# power_supply.net
KiCad netlist of a schematic drawn in Altium Designer
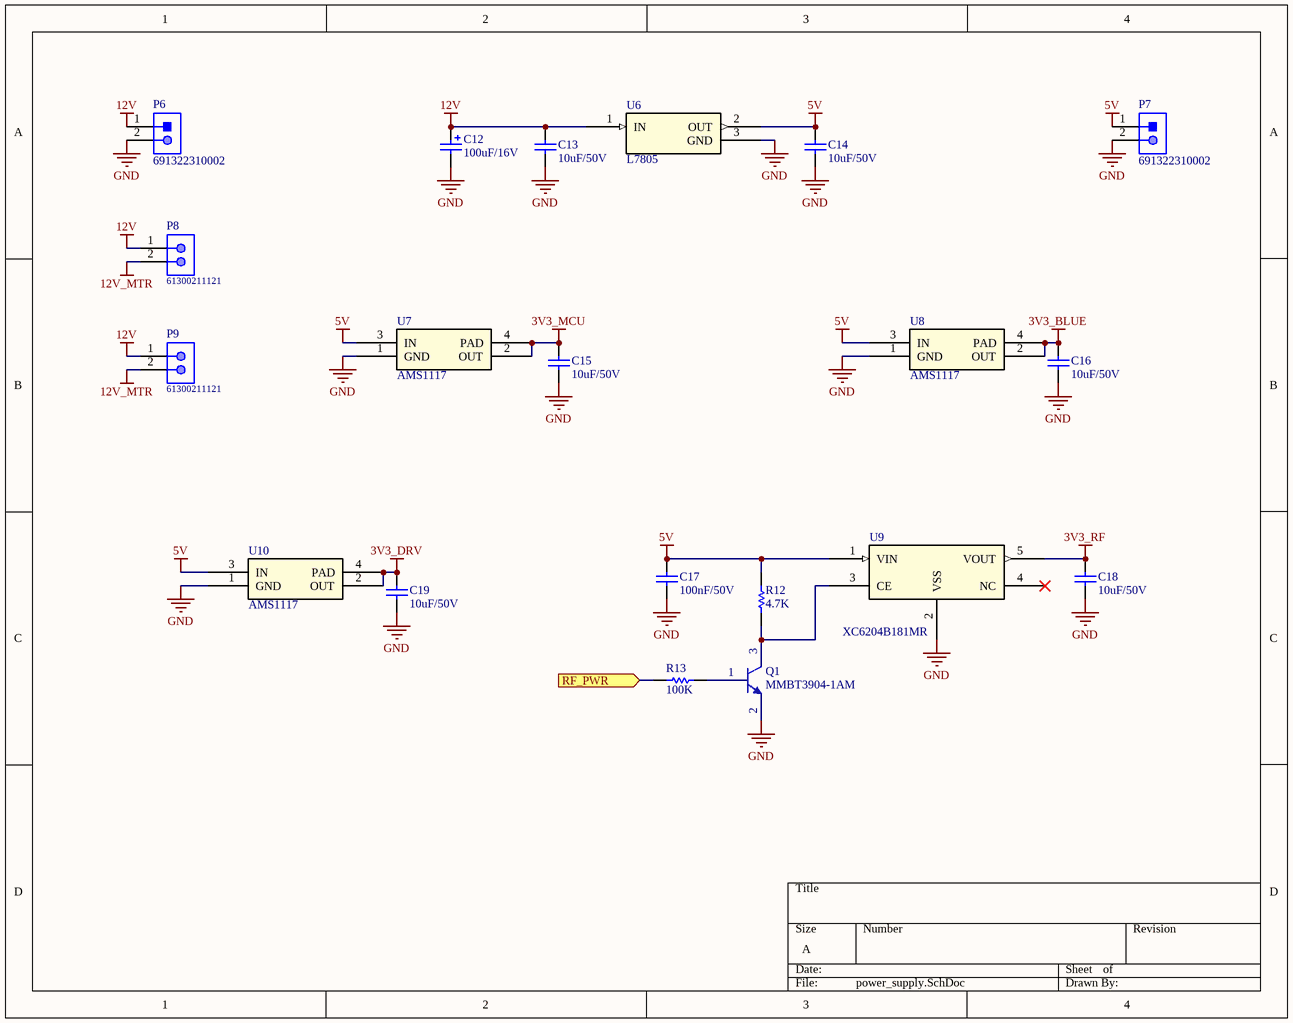
[diagram p0: power_supply.SchDoc]

(export (version "E")
  (design (tool "Eeschema 10.0.6"))
  (components
    (comp (ref "C12")
      (value "100uF/16V")
      (footprint "CAP-SM-AL-SIZE-D-D6L6")
      (description "CAP ALUM 100UF 20% 16V SMD")
      (fields
        (field (name "MANUFACTURER") "Nichicon")
        (field (name "MANUFACTURER PART NUMBER") "UWX1C101MCL1GB")
      )
      (libsource (lib "Capacitor") (part "Cap-Al-100uF-16V-D6L5"))
    )
    (comp (ref "C13")
      (value "10uF/50V")
      (footprint "CAP-SM-0805")
      (description "CAP CER 10UF 50V X5R 0805")
      (fields
        (field (name "MANUFACTURER") "Yageo")
        (field (name "MANUFACTURER PART NUMBER") "CC0805KKX5R9BB106")
      )
      (libsource (lib "Capacitor") (part "Cap-10uF-50V-0805"))
    )
    (comp (ref "C14")
      (value "10uF/50V")
      (footprint "CAP-SM-0805")
      (description "CAP CER 10UF 50V X5R 0805")
      (fields
        (field (name "MANUFACTURER") "Yageo")
        (field (name "MANUFACTURER PART NUMBER") "CC0805KKX5R9BB106")
      )
      (libsource (lib "Capacitor") (part "Cap-10uF-50V-0805"))
    )
    (comp (ref "C15")
      (value "10uF/50V")
      (footprint "CAP-SM-0805")
      (description "CAP CER 10UF 50V X5R 0805")
      (fields
        (field (name "MANUFACTURER") "Yageo")
        (field (name "MANUFACTURER PART NUMBER") "CC0805KKX5R9BB106")
      )
      (libsource (lib "Capacitor") (part "Cap-10uF-50V-0805"))
    )
    (comp (ref "C16")
      (value "10uF/50V")
      (footprint "CAP-SM-0805")
      (description "CAP CER 10UF 50V X5R 0805")
      (fields
        (field (name "MANUFACTURER") "Yageo")
        (field (name "MANUFACTURER PART NUMBER") "CC0805KKX5R9BB106")
      )
      (libsource (lib "Capacitor") (part "Cap-10uF-50V-0805"))
    )
    (comp (ref "C17")
      (value "100nF/50V")
      (footprint "CAP-SM-0805")
      (description "CAP CER 0.1UF 50V Y5V 0805")
      (fields
        (field (name "MANUFACTURER") "Samsung Electro-Mechanics")
        (field (name "MANUFACTURER PART NUMBER") "CL21F104ZBCNNNC")
      )
      (libsource (lib "Capacitor") (part "Cap-100nF-50V-0805"))
    )
    (comp (ref "C18")
      (value "10uF/50V")
      (footprint "CAP-SM-0805")
      (description "CAP CER 10UF 50V X5R 0805")
      (fields
        (field (name "MANUFACTURER") "Yageo")
        (field (name "MANUFACTURER PART NUMBER") "CC0805KKX5R9BB106")
      )
      (libsource (lib "Capacitor") (part "Cap-10uF-50V-0805"))
    )
    (comp (ref "C19")
      (value "10uF/50V")
      (footprint "CAP-SM-0805")
      (description "CAP CER 10UF 50V X5R 0805")
      (fields
        (field (name "MANUFACTURER") "Yageo")
        (field (name "MANUFACTURER PART NUMBER") "CC0805KKX5R9BB106")
      )
      (libsource (lib "Capacitor") (part "Cap-10uF-50V-0805"))
    )
    (comp (ref "P6")
      (value "691322310002")
      (footprint "691322310002")
      (description "WR-TBL Serie 322 Horizontal PCB Header, Pluggable, pitch 3.81mm, 2p")
      (fields (field (name "PUBLISHER") "Wurth Elektronik"))
      (libsource (lib "Wire_Protector") (part "691322310002"))
    )
    (comp (ref "P7")
      (value "691322310002")
      (footprint "691322310002")
      (description "WR-TBL Serie 322 Horizontal PCB Header, Pluggable, pitch 3.81mm, 2p")
      (fields (field (name "PUBLISHER") "Wurth Elektronik"))
      (libsource (lib "Wire_Protector") (part "691322310002"))
    )
    (comp (ref "P8")
      (value "61300211121")
      (footprint "61300211121")
      (description "WR-PHD Pin Header, THT, pitch 2.54mm, Single Row, Vertical, 2p")
      (fields (field (name "MANUFACTURER") "Wurth Elektronik"))
      (libsource (lib "Pluggable_Connector") (part "61300211121"))
    )
    (comp (ref "P9")
      (value "61300211121")
      (footprint "61300211121")
      (description "WR-PHD Pin Header, THT, pitch 2.54mm, Single Row, Vertical, 2p")
      (fields (field (name "MANUFACTURER") "Wurth Elektronik"))
      (libsource (lib "Pluggable_Connector") (part "61300211121"))
    )
    (comp (ref "Q1")
      (value "MMBT3904-1AM")
      (footprint "SOT23_NEX")
      (libsource (lib "Semiconductor") (part "MMBT3904-1AM"))
    )
    (comp (ref "R12")
      (value "4.7K")
      (footprint "Resistor:RES-SM-0805")
      (description "RES SMD 4.7K OHM 5% 1/8W 0805")
      (fields
        (field (name "MANUFACTURER") "Yageo")
        (field (name "MANUFACTURER PART NUMBER") "RC0805JR-074K7L")
      )
      (libsource (lib "Resistor") (part "Res-4.7K-0805"))
    )
    (comp (ref "R13")
      (value "100K")
      (footprint "Resistor:RES-SM-0805")
      (description "RES 0 OHM JUMPER 0805")
      (fields
        (field (name "MANUFACTURER") "Vishay Dale")
        (field (name "MANUFACTURER PART NUMBER") "WSL080500000ZEA9")
      )
      (libsource (lib "Resistor") (part "Res-100K-0805"))
    )
    (comp (ref "U6")
      (value "L7805")
      (footprint "L7805")
      (fields
        (field (name "MANUFACTURER_PART_NUMBER") "L7805CDT-TR")
        (field (name "COPYRIGHT") "Copyright (C) 2018 Accelerated Designs. All rights reserved")
      )
      (libsource (lib "IC") (part "L7805"))
    )
    (comp (ref "U7")
      (value "AMS1117")
      (footprint "AMS1117")
      (fields (field (name "COPYRIGHT") "Copyright (C) 2018 Accelerated Designs. All rights reserved"))
      (libsource (lib "IC") (part "AMS1117"))
    )
    (comp (ref "U8")
      (value "AMS1117")
      (footprint "AMS1117")
      (fields (field (name "COPYRIGHT") "Copyright (C) 2018 Accelerated Designs. All rights reserved"))
      (libsource (lib "IC") (part "AMS1117"))
    )
    (comp (ref "U9")
      (value "XC6204B181MR")
      (footprint "XC6204B181MR")
      (fields (field (name "COPYRIGHT") "Copyright (C) 2018 Accelerated Designs. All rights reserved"))
      (libsource (lib "IC") (part "XC6204B181MR"))
    )
    (comp (ref "U10")
      (value "AMS1117")
      (footprint "AMS1117")
      (fields (field (name "COPYRIGHT") "Copyright (C) 2018 Accelerated Designs. All rights reserved"))
      (libsource (lib "IC") (part "AMS1117"))
    )
  )
  (nets
    (net (code "1") (name "/RF_PWR") (class "Default")
      (node (ref "R13") (pin "1") (pinfunction "1_1") (pintype "passive"))
    )
    (net (code "2") (name "3V3_BLUE") (class "Default")
      (node (ref "C16") (pin "2") (pinfunction "2_2") (pintype "passive"))
      (node (ref "U8") (pin "2") (pinfunction "OUT_2") (pintype "passive"))
      (node (ref "U8") (pin "4") (pinfunction "PAD_4") (pintype "passive"))
    )
    (net (code "3") (name "3V3_DRV") (class "Default")
      (node (ref "C19") (pin "2") (pinfunction "2_2") (pintype "passive"))
      (node (ref "U10") (pin "2") (pinfunction "OUT_2") (pintype "passive"))
      (node (ref "U10") (pin "4") (pinfunction "PAD_4") (pintype "passive"))
    )
    (net (code "4") (name "3V3_MCU") (class "Default")
      (node (ref "C15") (pin "2") (pinfunction "2_2") (pintype "passive"))
      (node (ref "U7") (pin "2") (pinfunction "OUT_2") (pintype "passive"))
      (node (ref "U7") (pin "4") (pinfunction "PAD_4") (pintype "passive"))
    )
    (net (code "5") (name "3V3_RF") (class "Default")
      (node (ref "C18") (pin "2") (pinfunction "2_2") (pintype "passive"))
      (node (ref "U9") (pin "5") (pinfunction "VOUT_5") (pintype "output"))
    )
    (net (code "6") (name "5V") (class "Default")
      (node (ref "C14") (pin "2") (pinfunction "2_2") (pintype "passive"))
      (node (ref "C17") (pin "2") (pinfunction "2_2") (pintype "passive"))
      (node (ref "P7") (pin "1") (pinfunction "1_1") (pintype "passive"))
      (node (ref "R12") (pin "2") (pinfunction "2_2") (pintype "passive"))
      (node (ref "U10") (pin "3") (pinfunction "IN_3") (pintype "passive"))
      (node (ref "U6") (pin "2") (pinfunction "OUT_2") (pintype "output"))
      (node (ref "U7") (pin "3") (pinfunction "IN_3") (pintype "passive"))
      (node (ref "U8") (pin "3") (pinfunction "IN_3") (pintype "passive"))
      (node (ref "U9") (pin "1") (pinfunction "VIN_1") (pintype "input"))
    )
    (net (code "7") (name "12V") (class "Default")
      (node (ref "C12") (pin "1") (pinfunction "1_1") (pintype "passive"))
      (node (ref "C13") (pin "2") (pinfunction "2_2") (pintype "passive"))
      (node (ref "P6") (pin "1") (pinfunction "1_1") (pintype "passive"))
      (node (ref "P8") (pin "1") (pinfunction "1_1") (pintype "passive"))
      (node (ref "P9") (pin "1") (pinfunction "1_1") (pintype "passive"))
      (node (ref "U6") (pin "1") (pinfunction "IN_1") (pintype "input"))
    )
    (net (code "8") (name "12V_MTR") (class "Default")
      (node (ref "P8") (pin "2") (pinfunction "2_2") (pintype "passive"))
      (node (ref "P9") (pin "2") (pinfunction "2_2") (pintype "passive"))
    )
    (net (code "9") (name "GND") (class "Default")
      (node (ref "C12") (pin "2") (pinfunction "2_2") (pintype "passive"))
      (node (ref "C13") (pin "1") (pinfunction "1_1") (pintype "passive"))
      (node (ref "C14") (pin "1") (pinfunction "1_1") (pintype "passive"))
      (node (ref "C15") (pin "1") (pinfunction "1_1") (pintype "passive"))
      (node (ref "C16") (pin "1") (pinfunction "1_1") (pintype "passive"))
      (node (ref "C17") (pin "1") (pinfunction "1_1") (pintype "passive"))
      (node (ref "C18") (pin "1") (pinfunction "1_1") (pintype "passive"))
      (node (ref "C19") (pin "1") (pinfunction "1_1") (pintype "passive"))
      (node (ref "P6") (pin "2") (pinfunction "2_2") (pintype "passive"))
      (node (ref "P7") (pin "2") (pinfunction "2_2") (pintype "passive"))
      (node (ref "Q1") (pin "2") (pinfunction "E_2") (pintype "passive"))
      (node (ref "U10") (pin "1") (pinfunction "GND_1") (pintype "passive"))
      (node (ref "U6") (pin "3") (pinfunction "GND_3") (pintype "passive"))
      (node (ref "U7") (pin "1") (pinfunction "GND_1") (pintype "passive"))
      (node (ref "U8") (pin "1") (pinfunction "GND_1") (pintype "passive"))
      (node (ref "U9") (pin "2") (pinfunction "VSS_2") (pintype "passive"))
    )
    (net (code "10") (name "Net-(Q1-B)") (class "Default")
      (node (ref "Q1") (pin "1") (pinfunction "B_1") (pintype "passive"))
      (node (ref "R13") (pin "2") (pinfunction "2_2") (pintype "passive"))
    )
    (net (code "11") (name "Net-(Q1-C)") (class "Default")
      (node (ref "Q1") (pin "3") (pinfunction "C_3") (pintype "passive"))
      (node (ref "R12") (pin "1") (pinfunction "1_1") (pintype "passive"))
      (node (ref "U9") (pin "3") (pinfunction "CE_3") (pintype "passive"))
    )
    (net (code "12") (name "unconnected-(U9-NC-Pad4)") (class "Default")
      (node (ref "U9") (pin "4") (pinfunction "NC_4") (pintype "passive+no_connect"))
    )
  )
)
